# MCU.net
KiCad netlist of a schematic drawn in Altium Designer
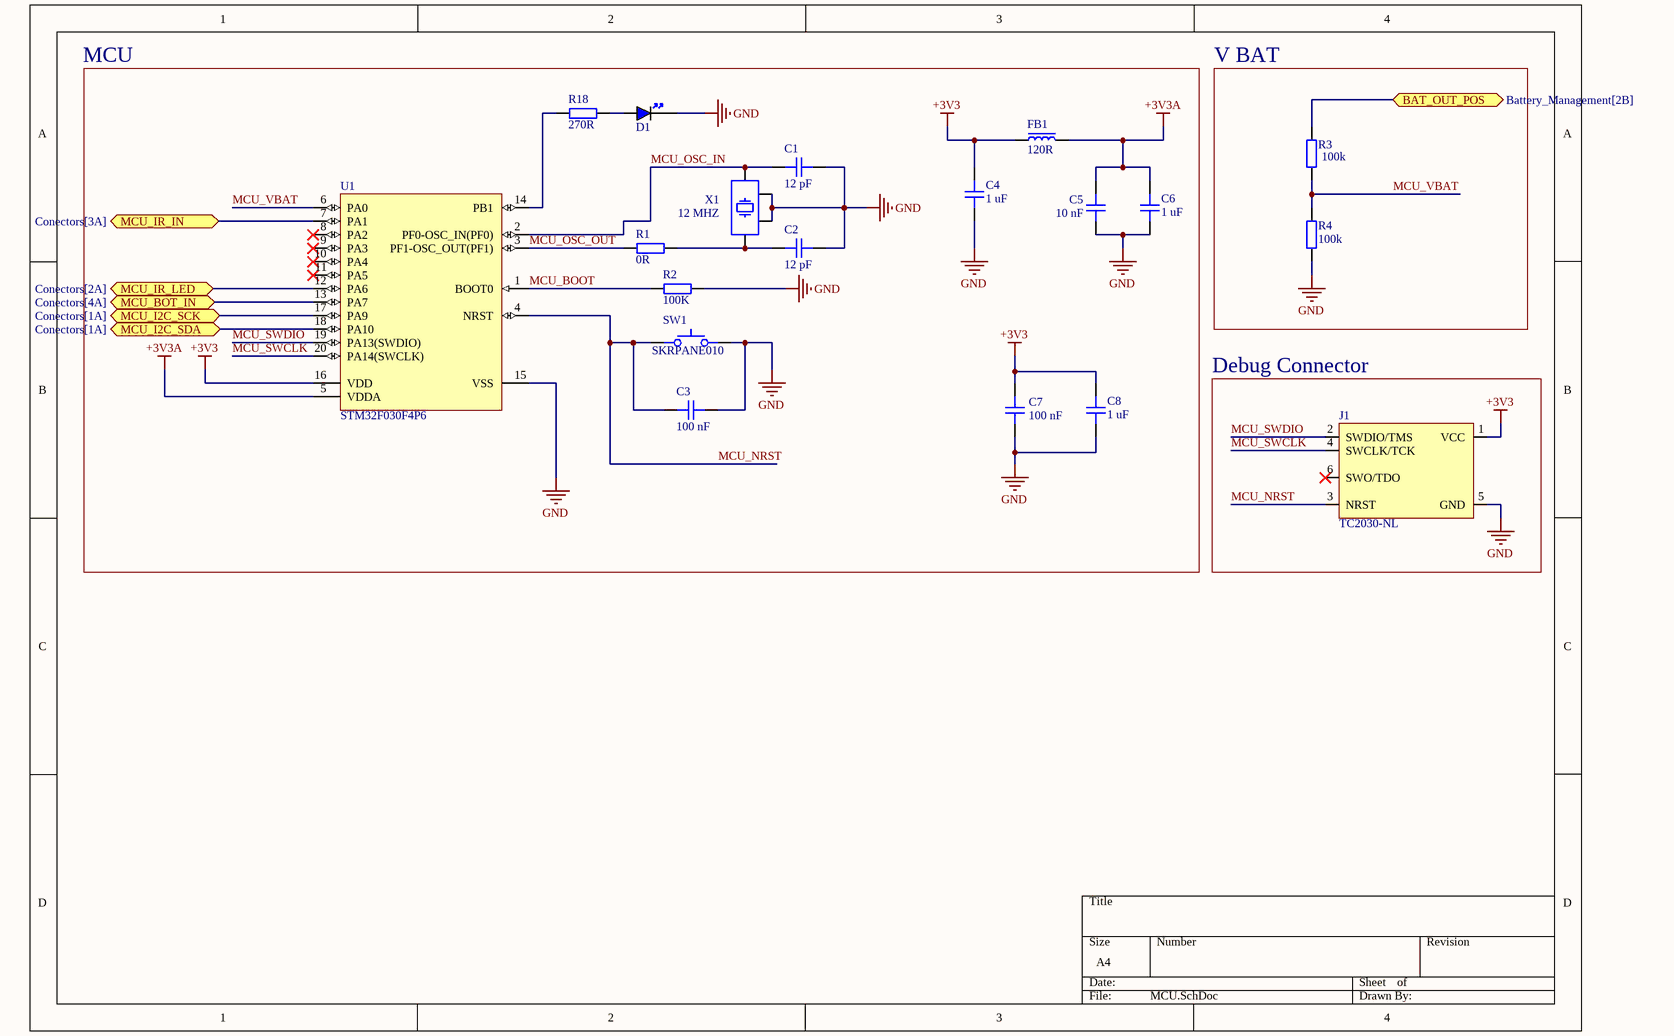
[diagram p0: MCU.SchDoc]

(export (version "E")
  (design (tool "Eeschema 10.0.6"))
  (components
    (comp (ref "C1")
      (value "12 pF")
      (footprint "CAP_0402")
      (description "Capacitor SMD 0402")
      (libsource (lib "Schematic-Lib-PhilsLab") (part "CAP_0402"))
    )
    (comp (ref "C2")
      (value "12 pF")
      (footprint "CAP_0402")
      (description "Capacitor SMD 0402")
      (libsource (lib "Schematic-Lib-PhilsLab") (part "CAP_0402"))
    )
    (comp (ref "C3")
      (value "100 nF")
      (footprint "CAP_0402")
      (description "Capacitor SMD 0402")
      (libsource (lib "Schematic-Lib-PhilsLab") (part "CAP_0402"))
    )
    (comp (ref "C4")
      (value "1 uF")
      (footprint "CAP_0805")
      (description "Capacitor SMD 0805")
      (libsource (lib "Schematic-Lib-PhilsLab") (part "CAP_0805"))
    )
    (comp (ref "C5")
      (value "10 nF")
      (footprint "CAP_0402")
      (description "Capacitor SMD 0402")
      (libsource (lib "Schematic-Lib-PhilsLab") (part "CAP_0402"))
    )
    (comp (ref "C6")
      (value "1 uF")
      (footprint "CAP_0805")
      (description "Capacitor SMD 0805")
      (libsource (lib "Schematic-Lib-PhilsLab") (part "CAP_0805"))
    )
    (comp (ref "C7")
      (value "100 nF")
      (footprint "CAP_0402")
      (description "Capacitor SMD 0402")
      (libsource (lib "Schematic-Lib-PhilsLab") (part "CAP_0402"))
    )
    (comp (ref "C8")
      (value "1 uF")
      (footprint "CAP_0805")
      (description "Capacitor SMD 0805")
      (libsource (lib "Schematic-Lib-PhilsLab") (part "CAP_0805"))
    )
    (comp (ref "D1")
      (value "BLUE")
      (footprint "LED_0805_BLUE")
      (description "LED 0805 BLUE SMD")
      (libsource (lib "Schematic-Lib-PhilsLab") (part "LED_0805_BLUE"))
    )
    (comp (ref "FB1")
      (value "120R")
      (footprint "FB_0805")
      (description "Ferrite Bead SMD 0805GZ2012D121TF")
      (fields (field (name "MANUFACTURER PART NUMBER") "PZ2012D121-3R0TF"))
      (libsource (lib "Schematic-Lib-PhilsLab") (part "FB_0805"))
    )
    (comp (ref "J1")
      (value "TC2030-NL")
      (footprint "TC2030-NL-FP")
      (description "Tag-Connect No-Solder SWD Debug Connector (No Legs) DO NOT PLACE")
      (fields
        (field (name "MANUFACTURER") "Tag-Connect")
        (field (name "MANUFACTURER PART NUMBER") "TC2030-NL-FP")
      )
      (libsource (lib "Schematic-Lib-PhilsLab") (part "TC2030-NL"))
    )
    (comp (ref "R1")
      (value "0R")
      (footprint "RES_0402")
      (description "Resistor SMD 0402")
      (libsource (lib "Schematic-Lib-PhilsLab") (part "RES_0402"))
    )
    (comp (ref "R2")
      (value "100K")
      (footprint "RES_0402")
      (description "Resistor SMD 0402")
      (libsource (lib "Schematic-Lib-PhilsLab") (part "RES_0402"))
    )
    (comp (ref "R3")
      (value "100k")
      (footprint "RES_0603")
      (description "Resistor SMD 0603")
      (libsource (lib "Schematic-Lib-PhilsLab") (part "RES_0603"))
    )
    (comp (ref "R4")
      (value "100k")
      (footprint "RES_0603")
      (description "Resistor SMD 0603")
      (libsource (lib "Schematic-Lib-PhilsLab") (part "RES_0603"))
    )
    (comp (ref "R18")
      (value "270R")
      (footprint "RES_0402")
      (description "Resistor SMD 0402")
      (libsource (lib "Schematic-Lib-PhilsLab") (part "RES_0402"))
    )
    (comp (ref "SW1")
      (value "SKRPANE010")
      (footprint "SKRPANE010")
      (description "Tactile Switch SMD SPST")
      (fields (field (name "MANUFACTURER") "Alps Alpine"))
      (libsource (lib "Schematic-Lib-PhilsLab") (part "SKRPANE010"))
    )
    (comp (ref "U1")
      (value "STM32F030F4P6")
      (footprint "STM-TSSOP20_L")
      (libsource (lib "Altium Content Vault") (part "MC-ARM-STM32F030-IL20"))
    )
    (comp (ref "X1")
      (value "12 MHZ")
      (footprint "XTAL_2520")
      (description "Crystal SMD 2520")
      (fields (field (name "MANUFACTURER PART NUMBER") "HY12MSMD2520FA1R30"))
      (libsource (lib "Schematic-Lib-PhilsLab") (part "XTAL_2520"))
    )
  )
  (nets
    (net (code "1") (name "+3V3") (class "Default")
      (node (ref "C4") (pin "2") (pinfunction "2_2") (pintype "passive"))
      (node (ref "C7") (pin "2") (pinfunction "2_2") (pintype "passive"))
      (node (ref "C8") (pin "2") (pinfunction "2_2") (pintype "passive"))
      (node (ref "FB1") (pin "1") (pinfunction "1_1") (pintype "passive"))
      (node (ref "J1") (pin "1") (pinfunction "VCC_1") (pintype "passive"))
      (node (ref "U1") (pin "16") (pinfunction "VDD_16") (pintype "power_in"))
    )
    (net (code "2") (name "+3V3A") (class "Default")
      (node (ref "C5") (pin "2") (pinfunction "2_2") (pintype "passive"))
      (node (ref "C6") (pin "2") (pinfunction "2_2") (pintype "passive"))
      (node (ref "FB1") (pin "2") (pinfunction "2_2") (pintype "passive"))
      (node (ref "U1") (pin "5") (pinfunction "VDDA_5") (pintype "power_in"))
    )
    (net (code "3") (name "/BAT_OUT_POS") (class "Default")
      (node (ref "R3") (pin "2") (pinfunction "2_2") (pintype "passive"))
    )
    (net (code "4") (name "/MCU_BOOT") (class "Default")
      (node (ref "R2") (pin "1") (pinfunction "1_1") (pintype "passive"))
      (node (ref "U1") (pin "1") (pinfunction "BOOT0_1") (pintype "input"))
    )
    (net (code "5") (name "/MCU_BOT_IN") (class "Default")
      (node (ref "U1") (pin "13") (pinfunction "PA7_13") (pintype "bidirectional"))
    )
    (net (code "6") (name "/MCU_I2C_SCK") (class "Default")
      (node (ref "U1") (pin "17") (pinfunction "PA9_17") (pintype "bidirectional"))
    )
    (net (code "7") (name "/MCU_I2C_SDA") (class "Default")
      (node (ref "U1") (pin "18") (pinfunction "PA10_18") (pintype "bidirectional"))
    )
    (net (code "8") (name "/MCU_IR_IN") (class "Default")
      (node (ref "U1") (pin "7") (pinfunction "PA1_7") (pintype "bidirectional"))
    )
    (net (code "9") (name "/MCU_IR_LED") (class "Default")
      (node (ref "U1") (pin "12") (pinfunction "PA6_12") (pintype "bidirectional"))
    )
    (net (code "10") (name "/MCU_NRST") (class "Default")
      (node (ref "C3") (pin "1") (pinfunction "1_1") (pintype "passive"))
      (node (ref "J1") (pin "3") (pinfunction "NRST_3") (pintype "passive"))
      (node (ref "SW1") (pin "12") (pintype "passive"))
      (node (ref "U1") (pin "4") (pinfunction "NRST_4") (pintype "bidirectional"))
    )
    (net (code "11") (name "/MCU_OSC_IN") (class "Default")
      (node (ref "C1") (pin "1") (pinfunction "1_1") (pintype "passive"))
      (node (ref "U1") (pin "2") (pinfunction "PF0-OSC_IN(PF0)_2") (pintype "bidirectional"))
      (node (ref "X1") (pin "3") (pinfunction "3_3") (pintype "passive"))
    )
    (net (code "12") (name "/MCU_OSC_OUT") (class "Default")
      (node (ref "R1") (pin "1") (pinfunction "1_1") (pintype "passive"))
      (node (ref "U1") (pin "3") (pinfunction "PF1-OSC_OUT(PF1)_3") (pintype "bidirectional"))
    )
    (net (code "13") (name "/MCU_SWCLK") (class "Default")
      (node (ref "J1") (pin "4") (pinfunction "SWCLK/TCK_4") (pintype "passive"))
      (node (ref "U1") (pin "20") (pinfunction "PA14(SWCLK)_20") (pintype "bidirectional"))
    )
    (net (code "14") (name "/MCU_SWDIO") (class "Default")
      (node (ref "J1") (pin "2") (pinfunction "SWDIO/TMS_2") (pintype "passive"))
      (node (ref "U1") (pin "19") (pinfunction "PA13(SWDIO)_19") (pintype "bidirectional"))
    )
    (net (code "15") (name "/MCU_VBAT") (class "Default")
      (node (ref "R3") (pin "1") (pinfunction "1_1") (pintype "passive"))
      (node (ref "R4") (pin "2") (pinfunction "2_2") (pintype "passive"))
      (node (ref "U1") (pin "6") (pinfunction "PA0_6") (pintype "bidirectional"))
    )
    (net (code "16") (name "GND") (class "Default")
      (node (ref "C1") (pin "2") (pinfunction "2_2") (pintype "passive"))
      (node (ref "C2") (pin "2") (pinfunction "2_2") (pintype "passive"))
      (node (ref "C3") (pin "2") (pinfunction "2_2") (pintype "passive"))
      (node (ref "C4") (pin "1") (pinfunction "1_1") (pintype "passive"))
      (node (ref "C5") (pin "1") (pinfunction "1_1") (pintype "passive"))
      (node (ref "C6") (pin "1") (pinfunction "1_1") (pintype "passive"))
      (node (ref "C7") (pin "1") (pinfunction "1_1") (pintype "passive"))
      (node (ref "C8") (pin "1") (pinfunction "1_1") (pintype "passive"))
      (node (ref "D1") (pin "K") (pinfunction "K_K") (pintype "passive"))
      (node (ref "J1") (pin "5") (pinfunction "GND_5") (pintype "passive"))
      (node (ref "R2") (pin "2") (pinfunction "2_2") (pintype "passive"))
      (node (ref "R4") (pin "1") (pinfunction "1_1") (pintype "passive"))
      (node (ref "SW1") (pin "34") (pintype "passive"))
      (node (ref "U1") (pin "15") (pinfunction "VSS_15") (pintype "power_in"))
      (node (ref "X1") (pin "2") (pinfunction "2_2") (pintype "passive"))
      (node (ref "X1") (pin "4") (pinfunction "4_4") (pintype "passive"))
    )
    (net (code "17") (name "Net-(C2-Pad1)") (class "Default")
      (node (ref "C2") (pin "1") (pinfunction "1_1") (pintype "passive"))
      (node (ref "R1") (pin "2") (pinfunction "2_2") (pintype "passive"))
      (node (ref "X1") (pin "1") (pinfunction "1_1") (pintype "passive"))
    )
    (net (code "18") (name "Net-(D1-PadA)") (class "Default")
      (node (ref "D1") (pin "A") (pinfunction "A_A") (pintype "passive"))
      (node (ref "R18") (pin "2") (pinfunction "2_2") (pintype "passive"))
    )
    (net (code "19") (name "Net-(U1-PB1)") (class "Default")
      (node (ref "R18") (pin "1") (pinfunction "1_1") (pintype "passive"))
      (node (ref "U1") (pin "14") (pinfunction "PB1_14") (pintype "bidirectional"))
    )
    (net (code "20") (name "unconnected-(J1-SWO{slash}TDO-Pad6)") (class "Default")
      (node (ref "J1") (pin "6") (pinfunction "SWO/TDO_6") (pintype "passive+no_connect"))
    )
    (net (code "21") (name "unconnected-(U1-PA2-Pad8)") (class "Default")
      (node (ref "U1") (pin "8") (pinfunction "PA2_8") (pintype "bidirectional+no_connect"))
    )
    (net (code "22") (name "unconnected-(U1-PA3-Pad9)") (class "Default")
      (node (ref "U1") (pin "9") (pinfunction "PA3_9") (pintype "bidirectional+no_connect"))
    )
    (net (code "23") (name "unconnected-(U1-PA4-Pad10)") (class "Default")
      (node (ref "U1") (pin "10") (pinfunction "PA4_10") (pintype "bidirectional+no_connect"))
    )
    (net (code "24") (name "unconnected-(U1-PA5-Pad11)") (class "Default")
      (node (ref "U1") (pin "11") (pinfunction "PA5_11") (pintype "bidirectional+no_connect"))
    )
  )
)
